# S151X.net
KiCad netlist of a schematic drawn in EAGLE
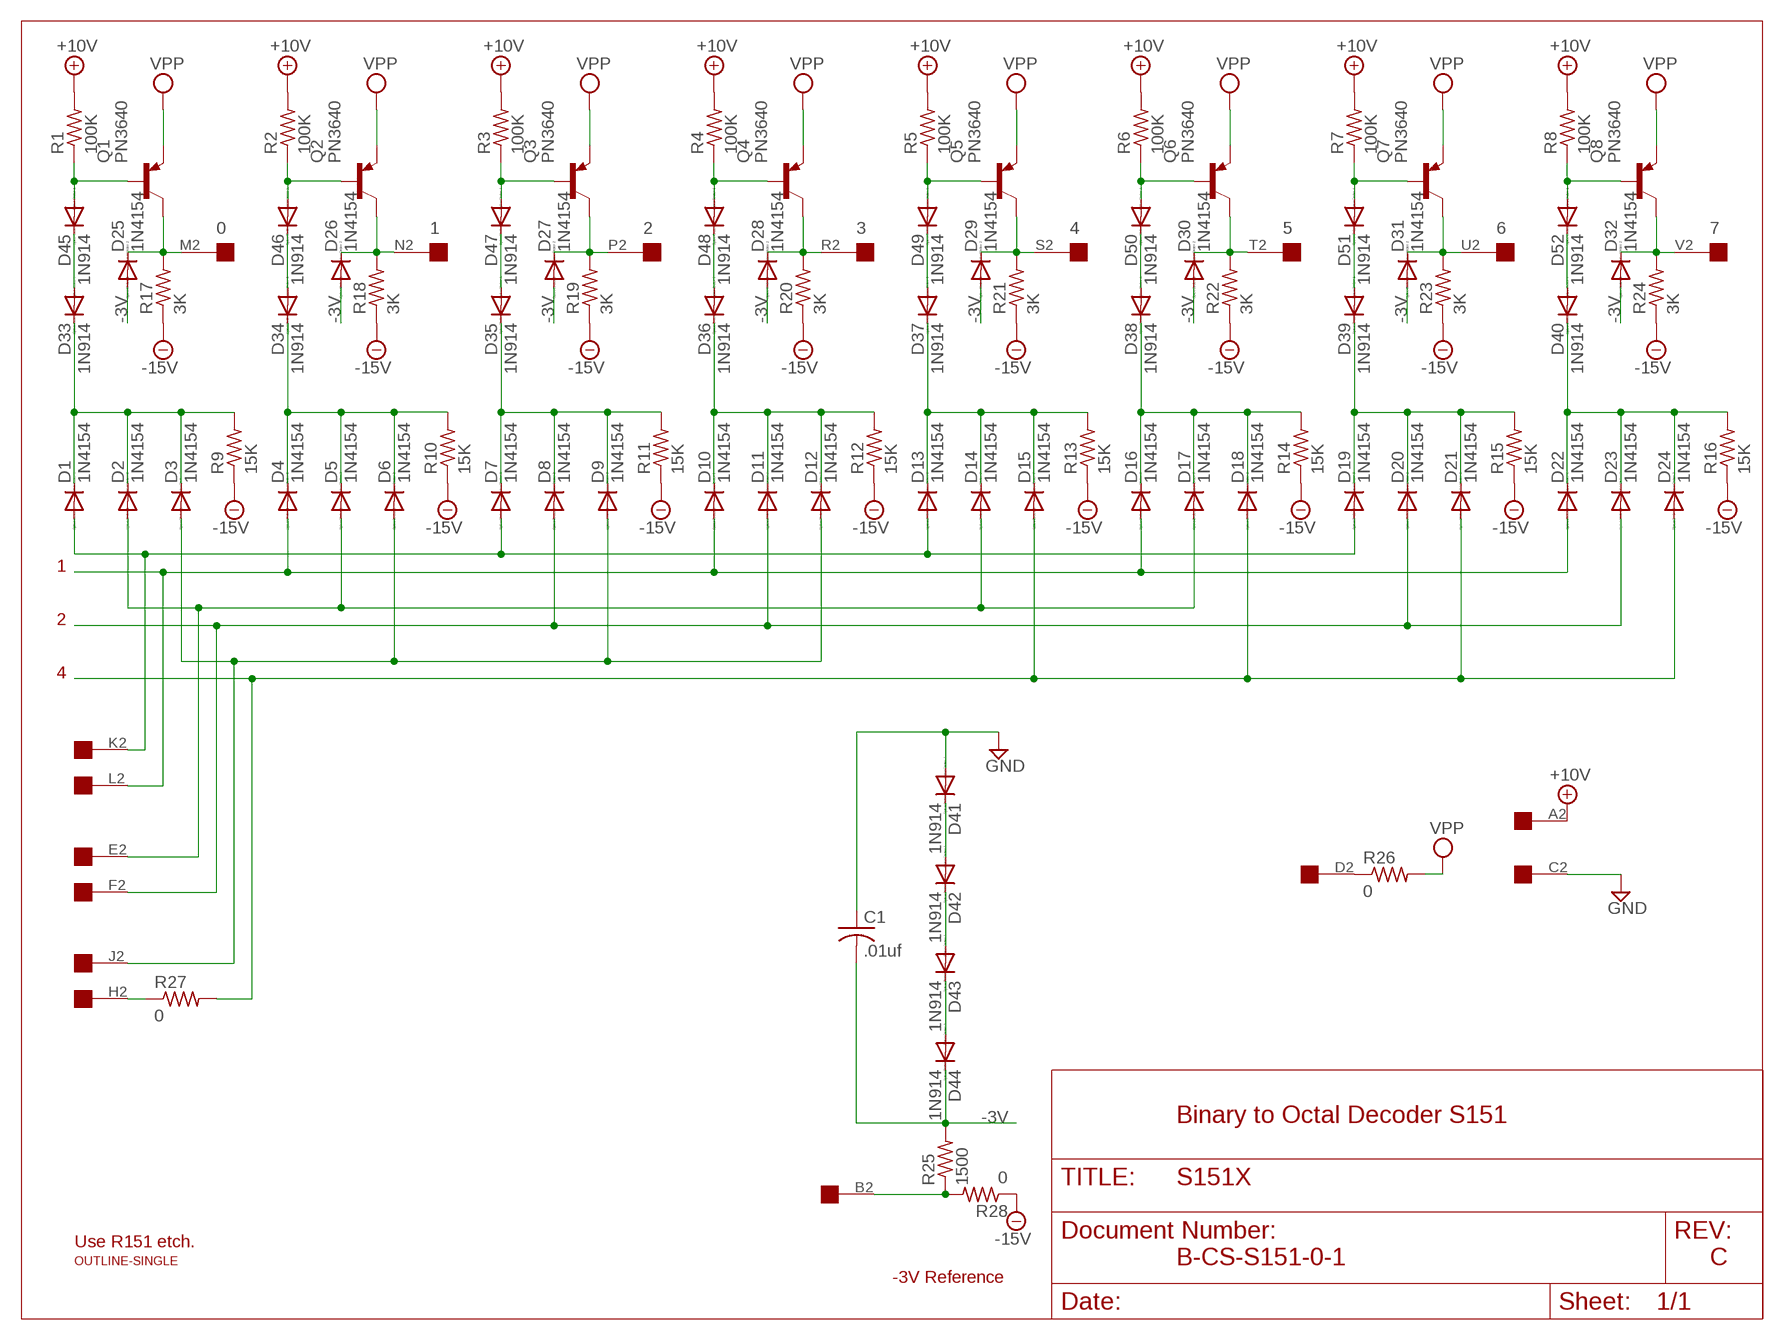
[diagram p0: schematic, sheet 1]

(export (version "E")
  (design (tool "Eeschema 10.0.6"))
  (components
    (comp (ref "C1")
      (value ".01uf")
      (footprint "eagle-import:C050-025X075")
      (libsource (lib "eagle-import") (part "C-US050-025X075"))
    )
    (comp (ref "D1")
      (value "1N4154")
      (footprint "eagle-import:DO35-10")
      (libsource (lib "eagle-import") (part "1N4148DO35-10"))
    )
    (comp (ref "D2")
      (value "1N4154")
      (footprint "eagle-import:DO35-10")
      (libsource (lib "eagle-import") (part "1N4148DO35-10"))
    )
    (comp (ref "D3")
      (value "1N4154")
      (footprint "eagle-import:DO35-10")
      (libsource (lib "eagle-import") (part "1N4148DO35-10"))
    )
    (comp (ref "D4")
      (value "1N4154")
      (footprint "eagle-import:DO35-10")
      (libsource (lib "eagle-import") (part "1N4148DO35-10"))
    )
    (comp (ref "D5")
      (value "1N4154")
      (footprint "eagle-import:DO35-10")
      (libsource (lib "eagle-import") (part "1N4148DO35-10"))
    )
    (comp (ref "D6")
      (value "1N4154")
      (footprint "eagle-import:DO35-10")
      (libsource (lib "eagle-import") (part "1N4148DO35-10"))
    )
    (comp (ref "D7")
      (value "1N4154")
      (footprint "eagle-import:DO35-10")
      (libsource (lib "eagle-import") (part "1N4148DO35-10"))
    )
    (comp (ref "D8")
      (value "1N4154")
      (footprint "eagle-import:DO35-10")
      (libsource (lib "eagle-import") (part "1N4148DO35-10"))
    )
    (comp (ref "D9")
      (value "1N4154")
      (footprint "eagle-import:DO35-10")
      (libsource (lib "eagle-import") (part "1N4148DO35-10"))
    )
    (comp (ref "D10")
      (value "1N4154")
      (footprint "eagle-import:DO35-10")
      (libsource (lib "eagle-import") (part "1N4148DO35-10"))
    )
    (comp (ref "D11")
      (value "1N4154")
      (footprint "eagle-import:DO35-10")
      (libsource (lib "eagle-import") (part "1N4148DO35-10"))
    )
    (comp (ref "D12")
      (value "1N4154")
      (footprint "eagle-import:DO35-10")
      (libsource (lib "eagle-import") (part "1N4148DO35-10"))
    )
    (comp (ref "D13")
      (value "1N4154")
      (footprint "eagle-import:DO35-10")
      (libsource (lib "eagle-import") (part "1N4148DO35-10"))
    )
    (comp (ref "D14")
      (value "1N4154")
      (footprint "eagle-import:DO35-10")
      (libsource (lib "eagle-import") (part "1N4148DO35-10"))
    )
    (comp (ref "D15")
      (value "1N4154")
      (footprint "eagle-import:DO35-10")
      (libsource (lib "eagle-import") (part "1N4148DO35-10"))
    )
    (comp (ref "D16")
      (value "1N4154")
      (footprint "eagle-import:DO35-10")
      (libsource (lib "eagle-import") (part "1N4148DO35-10"))
    )
    (comp (ref "D17")
      (value "1N4154")
      (footprint "eagle-import:DO35-10")
      (libsource (lib "eagle-import") (part "1N4148DO35-10"))
    )
    (comp (ref "D18")
      (value "1N4154")
      (footprint "eagle-import:DO35-10")
      (libsource (lib "eagle-import") (part "1N4148DO35-10"))
    )
    (comp (ref "D19")
      (value "1N4154")
      (footprint "eagle-import:DO35-10")
      (libsource (lib "eagle-import") (part "1N4148DO35-10"))
    )
    (comp (ref "D20")
      (value "1N4154")
      (footprint "eagle-import:DO35-10")
      (libsource (lib "eagle-import") (part "1N4148DO35-10"))
    )
    (comp (ref "D21")
      (value "1N4154")
      (footprint "eagle-import:DO35-10")
      (libsource (lib "eagle-import") (part "1N4148DO35-10"))
    )
    (comp (ref "D22")
      (value "1N4154")
      (footprint "eagle-import:DO35-10")
      (libsource (lib "eagle-import") (part "1N4148DO35-10"))
    )
    (comp (ref "D23")
      (value "1N4154")
      (footprint "eagle-import:DO35-10")
      (libsource (lib "eagle-import") (part "1N4148DO35-10"))
    )
    (comp (ref "D24")
      (value "1N4154")
      (footprint "eagle-import:DO35-10")
      (libsource (lib "eagle-import") (part "1N4148DO35-10"))
    )
    (comp (ref "D25")
      (value "1N4154")
      (footprint "eagle-import:DO35-10")
      (libsource (lib "eagle-import") (part "1N4148DO35-10"))
    )
    (comp (ref "D26")
      (value "1N4154")
      (footprint "eagle-import:DO35-10")
      (libsource (lib "eagle-import") (part "1N4148DO35-10"))
    )
    (comp (ref "D27")
      (value "1N4154")
      (footprint "eagle-import:DO35-10")
      (libsource (lib "eagle-import") (part "1N4148DO35-10"))
    )
    (comp (ref "D28")
      (value "1N4154")
      (footprint "eagle-import:DO35-10")
      (libsource (lib "eagle-import") (part "1N4148DO35-10"))
    )
    (comp (ref "D29")
      (value "1N4154")
      (footprint "eagle-import:DO35-10")
      (libsource (lib "eagle-import") (part "1N4148DO35-10"))
    )
    (comp (ref "D30")
      (value "1N4154")
      (footprint "eagle-import:DO35-10")
      (libsource (lib "eagle-import") (part "1N4148DO35-10"))
    )
    (comp (ref "D31")
      (value "1N4154")
      (footprint "eagle-import:DO35-10")
      (libsource (lib "eagle-import") (part "1N4148DO35-10"))
    )
    (comp (ref "D32")
      (value "1N4154")
      (footprint "eagle-import:DO35-10")
      (libsource (lib "eagle-import") (part "1N4148DO35-10"))
    )
    (comp (ref "D33")
      (value "1N914")
      (footprint "eagle-import:DO35-10")
      (libsource (lib "eagle-import") (part "1N4148DO35-10"))
    )
    (comp (ref "D34")
      (value "1N914")
      (footprint "eagle-import:DO35-10")
      (libsource (lib "eagle-import") (part "1N4148DO35-10"))
    )
    (comp (ref "D35")
      (value "1N914")
      (footprint "eagle-import:DO35-10")
      (libsource (lib "eagle-import") (part "1N4148DO35-10"))
    )
    (comp (ref "D36")
      (value "1N914")
      (footprint "eagle-import:DO35-10")
      (libsource (lib "eagle-import") (part "1N4148DO35-10"))
    )
    (comp (ref "D37")
      (value "1N914")
      (footprint "eagle-import:DO35-10")
      (libsource (lib "eagle-import") (part "1N4148DO35-10"))
    )
    (comp (ref "D38")
      (value "1N914")
      (footprint "eagle-import:DO35-10")
      (libsource (lib "eagle-import") (part "1N4148DO35-10"))
    )
    (comp (ref "D39")
      (value "1N914")
      (footprint "eagle-import:DO35-10")
      (libsource (lib "eagle-import") (part "1N4148DO35-10"))
    )
    (comp (ref "D40")
      (value "1N914")
      (footprint "eagle-import:DO35-10")
      (libsource (lib "eagle-import") (part "1N4148DO35-10"))
    )
    (comp (ref "D41")
      (value "1N914")
      (footprint "eagle-import:DO35-10")
      (libsource (lib "eagle-import") (part "1N4148DO35-10"))
    )
    (comp (ref "D42")
      (value "1N914")
      (footprint "eagle-import:DO35-10")
      (libsource (lib "eagle-import") (part "1N4148DO35-10"))
    )
    (comp (ref "D43")
      (value "1N914")
      (footprint "eagle-import:DO35-10")
      (libsource (lib "eagle-import") (part "1N4148DO35-10"))
    )
    (comp (ref "D44")
      (value "1N914")
      (footprint "eagle-import:DO35-10")
      (libsource (lib "eagle-import") (part "1N4148DO35-10"))
    )
    (comp (ref "D45")
      (value "1N914")
      (footprint "eagle-import:DO35-10")
      (libsource (lib "eagle-import") (part "1N4148DO35-10"))
    )
    (comp (ref "D46")
      (value "1N914")
      (footprint "eagle-import:DO35-10")
      (libsource (lib "eagle-import") (part "1N4148DO35-10"))
    )
    (comp (ref "D47")
      (value "1N914")
      (footprint "eagle-import:DO35-10")
      (libsource (lib "eagle-import") (part "1N4148DO35-10"))
    )
    (comp (ref "D48")
      (value "1N914")
      (footprint "eagle-import:DO35-10")
      (libsource (lib "eagle-import") (part "1N4148DO35-10"))
    )
    (comp (ref "D49")
      (value "1N914")
      (footprint "eagle-import:DO35-10")
      (libsource (lib "eagle-import") (part "1N4148DO35-10"))
    )
    (comp (ref "D50")
      (value "1N914")
      (footprint "eagle-import:DO35-10")
      (libsource (lib "eagle-import") (part "1N4148DO35-10"))
    )
    (comp (ref "D51")
      (value "1N914")
      (footprint "eagle-import:DO35-10")
      (libsource (lib "eagle-import") (part "1N4148DO35-10"))
    )
    (comp (ref "D52")
      (value "1N914")
      (footprint "eagle-import:DO35-10")
      (libsource (lib "eagle-import") (part "1N4148DO35-10"))
    )
    (comp (ref "Q1")
      (value "PN3640")
      (footprint "eagle-import:TO39")
      (libsource (lib "eagle-import") (part "2N3637"))
    )
    (comp (ref "Q2")
      (value "PN3640")
      (footprint "eagle-import:TO39")
      (libsource (lib "eagle-import") (part "2N3637"))
    )
    (comp (ref "Q3")
      (value "PN3640")
      (footprint "eagle-import:TO39")
      (libsource (lib "eagle-import") (part "2N3637"))
    )
    (comp (ref "Q4")
      (value "PN3640")
      (footprint "eagle-import:TO39")
      (libsource (lib "eagle-import") (part "2N3637"))
    )
    (comp (ref "Q5")
      (value "PN3640")
      (footprint "eagle-import:TO39")
      (libsource (lib "eagle-import") (part "2N3637"))
    )
    (comp (ref "Q6")
      (value "PN3640")
      (footprint "eagle-import:TO39")
      (libsource (lib "eagle-import") (part "2N3637"))
    )
    (comp (ref "Q7")
      (value "PN3640")
      (footprint "eagle-import:TO39")
      (libsource (lib "eagle-import") (part "2N3637"))
    )
    (comp (ref "Q8")
      (value "PN3640")
      (footprint "eagle-import:TO39")
      (libsource (lib "eagle-import") (part "2N3637"))
    )
    (comp (ref "R1")
      (value "100K")
      (footprint "eagle-import:0207_10")
      (libsource (lib "eagle-import") (part "R-US_0207/10"))
    )
    (comp (ref "R2")
      (value "100K")
      (footprint "eagle-import:0207_10")
      (libsource (lib "eagle-import") (part "R-US_0207/10"))
    )
    (comp (ref "R3")
      (value "100K")
      (footprint "eagle-import:0207_10")
      (libsource (lib "eagle-import") (part "R-US_0207/10"))
    )
    (comp (ref "R4")
      (value "100K")
      (footprint "eagle-import:0207_10")
      (libsource (lib "eagle-import") (part "R-US_0207/10"))
    )
    (comp (ref "R5")
      (value "100K")
      (footprint "eagle-import:0207_10")
      (libsource (lib "eagle-import") (part "R-US_0207/10"))
    )
    (comp (ref "R6")
      (value "100K")
      (footprint "eagle-import:0207_10")
      (libsource (lib "eagle-import") (part "R-US_0207/10"))
    )
    (comp (ref "R7")
      (value "100K")
      (footprint "eagle-import:0207_10")
      (libsource (lib "eagle-import") (part "R-US_0207/10"))
    )
    (comp (ref "R8")
      (value "100K")
      (footprint "eagle-import:0207_10")
      (libsource (lib "eagle-import") (part "R-US_0207/10"))
    )
    (comp (ref "R9")
      (value "15K")
      (footprint "eagle-import:0207_10")
      (libsource (lib "eagle-import") (part "R-US_0207/10"))
    )
    (comp (ref "R10")
      (value "15K")
      (footprint "eagle-import:0207_10")
      (libsource (lib "eagle-import") (part "R-US_0207/10"))
    )
    (comp (ref "R11")
      (value "15K")
      (footprint "eagle-import:0207_10")
      (libsource (lib "eagle-import") (part "R-US_0207/10"))
    )
    (comp (ref "R12")
      (value "15K")
      (footprint "eagle-import:0207_10")
      (libsource (lib "eagle-import") (part "R-US_0207/10"))
    )
    (comp (ref "R13")
      (value "15K")
      (footprint "eagle-import:0207_10")
      (libsource (lib "eagle-import") (part "R-US_0207/10"))
    )
    (comp (ref "R14")
      (value "15K")
      (footprint "eagle-import:0207_10")
      (libsource (lib "eagle-import") (part "R-US_0207/10"))
    )
    (comp (ref "R15")
      (value "15K")
      (footprint "eagle-import:0207_10")
      (libsource (lib "eagle-import") (part "R-US_0207/10"))
    )
    (comp (ref "R16")
      (value "15K")
      (footprint "eagle-import:0207_10")
      (libsource (lib "eagle-import") (part "R-US_0207/10"))
    )
    (comp (ref "R17")
      (value "3K")
      (footprint "eagle-import:0207_10")
      (libsource (lib "eagle-import") (part "R-US_0207/10"))
    )
    (comp (ref "R18")
      (value "3K")
      (footprint "eagle-import:0207_10")
      (libsource (lib "eagle-import") (part "R-US_0207/10"))
    )
    (comp (ref "R19")
      (value "3K")
      (footprint "eagle-import:0207_10")
      (libsource (lib "eagle-import") (part "R-US_0207/10"))
    )
    (comp (ref "R20")
      (value "3K")
      (footprint "eagle-import:0207_10")
      (libsource (lib "eagle-import") (part "R-US_0207/10"))
    )
    (comp (ref "R21")
      (value "3K")
      (footprint "eagle-import:0207_10")
      (libsource (lib "eagle-import") (part "R-US_0207/10"))
    )
    (comp (ref "R22")
      (value "3K")
      (footprint "eagle-import:0207_10")
      (libsource (lib "eagle-import") (part "R-US_0207/10"))
    )
    (comp (ref "R23")
      (value "3K")
      (footprint "eagle-import:0207_10")
      (libsource (lib "eagle-import") (part "R-US_0207/10"))
    )
    (comp (ref "R24")
      (value "3K")
      (footprint "eagle-import:0207_10")
      (libsource (lib "eagle-import") (part "R-US_0207/10"))
    )
    (comp (ref "R25")
      (value "1500")
      (footprint "eagle-import:0207_10")
      (libsource (lib "eagle-import") (part "R-US_0207/10"))
    )
    (comp (ref "R26")
      (value "0")
      (footprint "eagle-import:0207_10")
      (libsource (lib "eagle-import") (part "R-US_0207/10"))
    )
    (comp (ref "R27")
      (value "0")
      (footprint "eagle-import:0207_10")
      (libsource (lib "eagle-import") (part "R-US_0207/10"))
    )
    (comp (ref "R28")
      (value "0")
      (footprint "eagle-import:0207_10")
      (libsource (lib "eagle-import") (part "R-US_0207/10"))
    )
    (comp (ref "U$1")
      (value "OUTLINE-SINGLE")
      (footprint "eagle-import:SINGLE")
      (libsource (lib "eagle-import") (part "OUTLINE-SINGLE"))
    )
    (comp (ref "U$2")
      (value "EDGE-1")
      (footprint "eagle-import:EDGE-CON1")
      (libsource (lib "eagle-import") (part "EDGE-1"))
    )
  )
  (nets
    (net (code "1") (name "+10V") (class "Default")
      (node (ref "R1") (pin "2") (pinfunction "2_2") (pintype "passive"))
      (node (ref "R2") (pin "2") (pinfunction "2_2") (pintype "passive"))
      (node (ref "R3") (pin "2") (pinfunction "2_2") (pintype "passive"))
      (node (ref "R4") (pin "2") (pinfunction "2_2") (pintype "passive"))
      (node (ref "R5") (pin "2") (pinfunction "2_2") (pintype "passive"))
      (node (ref "R6") (pin "2") (pinfunction "2_2") (pintype "passive"))
      (node (ref "R7") (pin "2") (pinfunction "2_2") (pintype "passive"))
      (node (ref "R8") (pin "2") (pinfunction "2_2") (pintype "passive"))
      (node (ref "U$2") (pin "A2") (pinfunction "1_A2") (pintype "bidirectional"))
    )
    (net (code "2") (name "-15V") (class "Default")
      (node (ref "R10") (pin "1") (pinfunction "1_1") (pintype "passive"))
      (node (ref "R11") (pin "1") (pinfunction "1_1") (pintype "passive"))
      (node (ref "R12") (pin "1") (pinfunction "1_1") (pintype "passive"))
      (node (ref "R13") (pin "1") (pinfunction "1_1") (pintype "passive"))
      (node (ref "R14") (pin "1") (pinfunction "1_1") (pintype "passive"))
      (node (ref "R15") (pin "1") (pinfunction "1_1") (pintype "passive"))
      (node (ref "R16") (pin "1") (pinfunction "1_1") (pintype "passive"))
      (node (ref "R17") (pin "1") (pinfunction "1_1") (pintype "passive"))
      (node (ref "R18") (pin "1") (pinfunction "1_1") (pintype "passive"))
      (node (ref "R19") (pin "1") (pinfunction "1_1") (pintype "passive"))
      (node (ref "R20") (pin "1") (pinfunction "1_1") (pintype "passive"))
      (node (ref "R21") (pin "1") (pinfunction "1_1") (pintype "passive"))
      (node (ref "R22") (pin "1") (pinfunction "1_1") (pintype "passive"))
      (node (ref "R23") (pin "1") (pinfunction "1_1") (pintype "passive"))
      (node (ref "R24") (pin "1") (pinfunction "1_1") (pintype "passive"))
      (node (ref "R28") (pin "1") (pinfunction "1_1") (pintype "passive"))
      (node (ref "R9") (pin "1") (pinfunction "1_1") (pintype "passive"))
    )
    (net (code "3") (name "/-3V") (class "Default")
      (node (ref "C1") (pin "2") (pinfunction "2_2") (pintype "passive"))
      (node (ref "D25") (pin "A") (pinfunction "A_A") (pintype "passive"))
      (node (ref "D26") (pin "A") (pinfunction "A_A") (pintype "passive"))
      (node (ref "D27") (pin "A") (pinfunction "A_A") (pintype "passive"))
      (node (ref "D28") (pin "A") (pinfunction "A_A") (pintype "passive"))
      (node (ref "D29") (pin "A") (pinfunction "A_A") (pintype "passive"))
      (node (ref "D30") (pin "A") (pinfunction "A_A") (pintype "passive"))
      (node (ref "D31") (pin "A") (pinfunction "A_A") (pintype "passive"))
      (node (ref "D32") (pin "A") (pinfunction "A_A") (pintype "passive"))
      (node (ref "D44") (pin "C") (pinfunction "C_C") (pintype "passive"))
      (node (ref "R25") (pin "2") (pinfunction "2_2") (pintype "passive"))
    )
    (net (code "4") (name "/0") (class "Default")
      (node (ref "D25") (pin "C") (pinfunction "C_C") (pintype "passive"))
      (node (ref "Q1") (pin "3") (pinfunction "C_3") (pintype "passive"))
      (node (ref "R17") (pin "2") (pinfunction "2_2") (pintype "passive"))
      (node (ref "U$2") (pin "M2") (pinfunction "1_M2") (pintype "bidirectional"))
    )
    (net (code "5") (name "/1") (class "Default")
      (node (ref "D26") (pin "C") (pinfunction "C_C") (pintype "passive"))
      (node (ref "Q2") (pin "3") (pinfunction "C_3") (pintype "passive"))
      (node (ref "R18") (pin "2") (pinfunction "2_2") (pintype "passive"))
      (node (ref "U$2") (pin "N2") (pinfunction "1_N2") (pintype "bidirectional"))
    )
    (net (code "6") (name "/2") (class "Default")
      (node (ref "D27") (pin "C") (pinfunction "C_C") (pintype "passive"))
      (node (ref "Q3") (pin "3") (pinfunction "C_3") (pintype "passive"))
      (node (ref "R19") (pin "2") (pinfunction "2_2") (pintype "passive"))
      (node (ref "U$2") (pin "P2") (pinfunction "1_P2") (pintype "bidirectional"))
    )
    (net (code "7") (name "/3") (class "Default")
      (node (ref "D28") (pin "C") (pinfunction "C_C") (pintype "passive"))
      (node (ref "Q4") (pin "3") (pinfunction "C_3") (pintype "passive"))
      (node (ref "R20") (pin "2") (pinfunction "2_2") (pintype "passive"))
      (node (ref "U$2") (pin "R2") (pinfunction "1_R2") (pintype "bidirectional"))
    )
    (net (code "8") (name "/4") (class "Default")
      (node (ref "D29") (pin "C") (pinfunction "C_C") (pintype "passive"))
      (node (ref "Q5") (pin "3") (pinfunction "C_3") (pintype "passive"))
      (node (ref "R21") (pin "2") (pinfunction "2_2") (pintype "passive"))
      (node (ref "U$2") (pin "S2") (pinfunction "1_S2") (pintype "bidirectional"))
    )
    (net (code "9") (name "/5") (class "Default")
      (node (ref "D30") (pin "C") (pinfunction "C_C") (pintype "passive"))
      (node (ref "Q6") (pin "3") (pinfunction "C_3") (pintype "passive"))
      (node (ref "R22") (pin "2") (pinfunction "2_2") (pintype "passive"))
      (node (ref "U$2") (pin "T2") (pinfunction "1_T2") (pintype "bidirectional"))
    )
    (net (code "10") (name "/6") (class "Default")
      (node (ref "D31") (pin "C") (pinfunction "C_C") (pintype "passive"))
      (node (ref "Q7") (pin "3") (pinfunction "C_3") (pintype "passive"))
      (node (ref "R23") (pin "2") (pinfunction "2_2") (pintype "passive"))
      (node (ref "U$2") (pin "U2") (pinfunction "1_U2") (pintype "bidirectional"))
    )
    (net (code "11") (name "/7") (class "Default")
      (node (ref "D32") (pin "C") (pinfunction "C_C") (pintype "passive"))
      (node (ref "Q8") (pin "3") (pinfunction "C_3") (pintype "passive"))
      (node (ref "R24") (pin "2") (pinfunction "2_2") (pintype "passive"))
      (node (ref "U$2") (pin "V2") (pinfunction "1_V2") (pintype "bidirectional"))
    )
    (net (code "12") (name "GND") (class "Default")
      (node (ref "C1") (pin "1") (pinfunction "1_1") (pintype "passive"))
      (node (ref "D41") (pin "A") (pinfunction "A_A") (pintype "passive"))
      (node (ref "U$2") (pin "C2") (pinfunction "1_C2") (pintype "bidirectional"))
    )
    (net (code "13") (name "Net-(D1-PadC)") (class "Default")
      (node (ref "D1") (pin "C") (pinfunction "C_C") (pintype "passive"))
      (node (ref "D2") (pin "C") (pinfunction "C_C") (pintype "passive"))
      (node (ref "D3") (pin "C") (pinfunction "C_C") (pintype "passive"))
      (node (ref "D33") (pin "C") (pinfunction "C_C") (pintype "passive"))
      (node (ref "R9") (pin "2") (pinfunction "2_2") (pintype "passive"))
    )
    (net (code "14") (name "Net-(D10-PadC)") (class "Default")
      (node (ref "D10") (pin "C") (pinfunction "C_C") (pintype "passive"))
      (node (ref "D11") (pin "C") (pinfunction "C_C") (pintype "passive"))
      (node (ref "D12") (pin "C") (pinfunction "C_C") (pintype "passive"))
      (node (ref "D36") (pin "C") (pinfunction "C_C") (pintype "passive"))
      (node (ref "R12") (pin "2") (pinfunction "2_2") (pintype "passive"))
    )
    (net (code "15") (name "Net-(D13-PadC)") (class "Default")
      (node (ref "D13") (pin "C") (pinfunction "C_C") (pintype "passive"))
      (node (ref "D14") (pin "C") (pinfunction "C_C") (pintype "passive"))
      (node (ref "D15") (pin "C") (pinfunction "C_C") (pintype "passive"))
      (node (ref "D37") (pin "C") (pinfunction "C_C") (pintype "passive"))
      (node (ref "R13") (pin "2") (pinfunction "2_2") (pintype "passive"))
    )
    (net (code "16") (name "Net-(D15-PadA)") (class "Default")
      (node (ref "D15") (pin "A") (pinfunction "A_A") (pintype "passive"))
      (node (ref "D18") (pin "A") (pinfunction "A_A") (pintype "passive"))
      (node (ref "D21") (pin "A") (pinfunction "A_A") (pintype "passive"))
      (node (ref "D24") (pin "A") (pinfunction "A_A") (pintype "passive"))
      (node (ref "R27") (pin "2") (pinfunction "2_2") (pintype "passive"))
    )
    (net (code "17") (name "Net-(D16-PadC)") (class "Default")
      (node (ref "D16") (pin "C") (pinfunction "C_C") (pintype "passive"))
      (node (ref "D17") (pin "C") (pinfunction "C_C") (pintype "passive"))
      (node (ref "D18") (pin "C") (pinfunction "C_C") (pintype "passive"))
      (node (ref "D38") (pin "C") (pinfunction "C_C") (pintype "passive"))
      (node (ref "R14") (pin "2") (pinfunction "2_2") (pintype "passive"))
    )
    (net (code "18") (name "Net-(D19-PadC)") (class "Default")
      (node (ref "D19") (pin "C") (pinfunction "C_C") (pintype "passive"))
      (node (ref "D20") (pin "C") (pinfunction "C_C") (pintype "passive"))
      (node (ref "D21") (pin "C") (pinfunction "C_C") (pintype "passive"))
      (node (ref "D39") (pin "C") (pinfunction "C_C") (pintype "passive"))
      (node (ref "R15") (pin "2") (pinfunction "2_2") (pintype "passive"))
    )
    (net (code "19") (name "Net-(D22-PadC)") (class "Default")
      (node (ref "D22") (pin "C") (pinfunction "C_C") (pintype "passive"))
      (node (ref "D23") (pin "C") (pinfunction "C_C") (pintype "passive"))
      (node (ref "D24") (pin "C") (pinfunction "C_C") (pintype "passive"))
      (node (ref "D40") (pin "C") (pinfunction "C_C") (pintype "passive"))
      (node (ref "R16") (pin "2") (pinfunction "2_2") (pintype "passive"))
    )
    (net (code "20") (name "Net-(D33-PadA)") (class "Default")
      (node (ref "D33") (pin "A") (pinfunction "A_A") (pintype "passive"))
      (node (ref "D45") (pin "C") (pinfunction "C_C") (pintype "passive"))
    )
    (net (code "21") (name "Net-(D34-PadA)") (class "Default")
      (node (ref "D34") (pin "A") (pinfunction "A_A") (pintype "passive"))
      (node (ref "D46") (pin "C") (pinfunction "C_C") (pintype "passive"))
    )
    (net (code "22") (name "Net-(D34-PadC)") (class "Default")
      (node (ref "D34") (pin "C") (pinfunction "C_C") (pintype "passive"))
      (node (ref "D4") (pin "C") (pinfunction "C_C") (pintype "passive"))
      (node (ref "D5") (pin "C") (pinfunction "C_C") (pintype "passive"))
      (node (ref "D6") (pin "C") (pinfunction "C_C") (pintype "passive"))
      (node (ref "R10") (pin "2") (pinfunction "2_2") (pintype "passive"))
    )
    (net (code "23") (name "Net-(D35-PadA)") (class "Default")
      (node (ref "D35") (pin "A") (pinfunction "A_A") (pintype "passive"))
      (node (ref "D47") (pin "C") (pinfunction "C_C") (pintype "passive"))
    )
    (net (code "24") (name "Net-(D35-PadC)") (class "Default")
      (node (ref "D35") (pin "C") (pinfunction "C_C") (pintype "passive"))
      (node (ref "D7") (pin "C") (pinfunction "C_C") (pintype "passive"))
      (node (ref "D8") (pin "C") (pinfunction "C_C") (pintype "passive"))
      (node (ref "D9") (pin "C") (pinfunction "C_C") (pintype "passive"))
      (node (ref "R11") (pin "2") (pinfunction "2_2") (pintype "passive"))
    )
    (net (code "25") (name "Net-(D36-PadA)") (class "Default")
      (node (ref "D36") (pin "A") (pinfunction "A_A") (pintype "passive"))
      (node (ref "D48") (pin "C") (pinfunction "C_C") (pintype "passive"))
    )
    (net (code "26") (name "Net-(D37-PadA)") (class "Default")
      (node (ref "D37") (pin "A") (pinfunction "A_A") (pintype "passive"))
      (node (ref "D49") (pin "C") (pinfunction "C_C") (pintype "passive"))
    )
    (net (code "27") (name "Net-(D38-PadA)") (class "Default")
      (node (ref "D38") (pin "A") (pinfunction "A_A") (pintype "passive"))
      (node (ref "D50") (pin "C") (pinfunction "C_C") (pintype "passive"))
    )
    (net (code "28") (name "Net-(D39-PadA)") (class "Default")
      (node (ref "D39") (pin "A") (pinfunction "A_A") (pintype "passive"))
      (node (ref "D51") (pin "C") (pinfunction "C_C") (pintype "passive"))
    )
    (net (code "29") (name "Net-(D40-PadA)") (class "Default")
      (node (ref "D40") (pin "A") (pinfunction "A_A") (pintype "passive"))
      (node (ref "D52") (pin "C") (pinfunction "C_C") (pintype "passive"))
    )
    (net (code "30") (name "Net-(D41-PadC)") (class "Default")
      (node (ref "D41") (pin "C") (pinfunction "C_C") (pintype "passive"))
      (node (ref "D42") (pin "A") (pinfunction "A_A") (pintype "passive"))
    )
    (net (code "31") (name "Net-(D42-PadC)") (class "Default")
      (node (ref "D42") (pin "C") (pinfunction "C_C") (pintype "passive"))
      (node (ref "D43") (pin "A") (pinfunction "A_A") (pintype "passive"))
    )
    (net (code "32") (name "Net-(D43-PadC)") (class "Default")
      (node (ref "D43") (pin "C") (pinfunction "C_C") (pintype "passive"))
      (node (ref "D44") (pin "A") (pinfunction "A_A") (pintype "passive"))
    )
    (net (code "33") (name "Net-(Q1-B)") (class "Default")
      (node (ref "D45") (pin "A") (pinfunction "A_A") (pintype "passive"))
      (node (ref "Q1") (pin "2") (pinfunction "B_2") (pintype "passive"))
      (node (ref "R1") (pin "1") (pinfunction "1_1") (pintype "passive"))
    )
    (net (code "34") (name "Net-(Q2-B)") (class "Default")
      (node (ref "D46") (pin "A") (pinfunction "A_A") (pintype "passive"))
      (node (ref "Q2") (pin "2") (pinfunction "B_2") (pintype "passive"))
      (node (ref "R2") (pin "1") (pinfunction "1_1") (pintype "passive"))
    )
    (net (code "35") (name "Net-(Q3-B)") (class "Default")
      (node (ref "D47") (pin "A") (pinfunction "A_A") (pintype "passive"))
      (node (ref "Q3") (pin "2") (pinfunction "B_2") (pintype "passive"))
      (node (ref "R3") (pin "1") (pinfunction "1_1") (pintype "passive"))
    )
    (net (code "36") (name "Net-(Q4-B)") (class "Default")
      (node (ref "D48") (pin "A") (pinfunction "A_A") (pintype "passive"))
      (node (ref "Q4") (pin "2") (pinfunction "B_2") (pintype "passive"))
      (node (ref "R4") (pin "1") (pinfunction "1_1") (pintype "passive"))
    )
    (net (code "37") (name "Net-(Q5-B)") (class "Default")
      (node (ref "D49") (pin "A") (pinfunction "A_A") (pintype "passive"))
      (node (ref "Q5") (pin "2") (pinfunction "B_2") (pintype "passive"))
      (node (ref "R5") (pin "1") (pinfunction "1_1") (pintype "passive"))
    )
    (net (code "38") (name "Net-(Q6-B)") (class "Default")
      (node (ref "D50") (pin "A") (pinfunction "A_A") (pintype "passive"))
      (node (ref "Q6") (pin "2") (pinfunction "B_2") (pintype "passive"))
      (node (ref "R6") (pin "1") (pinfunction "1_1") (pintype "passive"))
    )
    (net (code "39") (name "Net-(Q7-B)") (class "Default")
      (node (ref "D51") (pin "A") (pinfunction "A_A") (pintype "passive"))
      (node (ref "Q7") (pin "2") (pinfunction "B_2") (pintype "passive"))
      (node (ref "R7") (pin "1") (pinfunction "1_1") (pintype "passive"))
    )
    (net (code "40") (name "Net-(Q8-B)") (class "Default")
      (node (ref "D52") (pin "A") (pinfunction "A_A") (pintype "passive"))
      (node (ref "Q8") (pin "2") (pinfunction "B_2") (pintype "passive"))
      (node (ref "R8") (pin "1") (pinfunction "1_1") (pintype "passive"))
    )
    (net (code "41") (name "Net-(U$2B-1)") (class "Default")
      (node (ref "R25") (pin "1") (pinfunction "1_1") (pintype "passive"))
      (node (ref "R28") (pin "2") (pinfunction "2_2") (pintype "passive"))
      (node (ref "U$2") (pin "B2") (pinfunction "1_B2") (pintype "bidirectional"))
    )
    (net (code "42") (name "Net-(U$2D-1)") (class "Default")
      (node (ref "R26") (pin "1") (pinfunction "1_1") (pintype "passive"))
      (node (ref "U$2") (pin "D2") (pinfunction "1_D2") (pintype "bidirectional"))
    )
    (net (code "43") (name "Net-(U$2E-1)") (class "Default")
      (node (ref "D14") (pin "A") (pinfunction "A_A") (pintype "passive"))
      (node (ref "D17") (pin "A") (pinfunction "A_A") (pintype "passive"))
      (node (ref "D2") (pin "A") (pinfunction "A_A") (pintype "passive"))
      (node (ref "D5") (pin "A") (pinfunction "A_A") (pintype "passive"))
      (node (ref "U$2") (pin "E2") (pinfunction "1_E2") (pintype "bidirectional"))
    )
    (net (code "44") (name "Net-(U$2F-1)") (class "Default")
      (node (ref "D11") (pin "A") (pinfunction "A_A") (pintype "passive"))
      (node (ref "D20") (pin "A") (pinfunction "A_A") (pintype "passive"))
      (node (ref "D23") (pin "A") (pinfunction "A_A") (pintype "passive"))
      (node (ref "D8") (pin "A") (pinfunction "A_A") (pintype "passive"))
      (node (ref "U$2") (pin "F2") (pinfunction "1_F2") (pintype "bidirectional"))
    )
    (net (code "45") (name "Net-(U$2G-1)") (class "Default")
      (node (ref "R27") (pin "1") (pinfunction "1_1") (pintype "passive"))
      (node (ref "U$2") (pin "H2") (pinfunction "1_H2") (pintype "bidirectional"))
    )
    (net (code "46") (name "Net-(U$2H-1)") (class "Default")
      (node (ref "D12") (pin "A") (pinfunction "A_A") (pintype "passive"))
      (node (ref "D3") (pin "A") (pinfunction "A_A") (pintype "passive"))
      (node (ref "D6") (pin "A") (pinfunction "A_A") (pintype "passive"))
      (node (ref "D9") (pin "A") (pinfunction "A_A") (pintype "passive"))
      (node (ref "U$2") (pin "J2") (pinfunction "1_J2") (pintype "bidirectional"))
    )
    (net (code "47") (name "Net-(U$2I-1)") (class "Default")
      (node (ref "D1") (pin "A") (pinfunction "A_A") (pintype "passive"))
      (node (ref "D13") (pin "A") (pinfunction "A_A") (pintype "passive"))
      (node (ref "D19") (pin "A") (pinfunction "A_A") (pintype "passive"))
      (node (ref "D7") (pin "A") (pinfunction "A_A") (pintype "passive"))
      (node (ref "U$2") (pin "K2") (pinfunction "1_K2") (pintype "bidirectional"))
    )
    (net (code "48") (name "Net-(U$2J-1)") (class "Default")
      (node (ref "D10") (pin "A") (pinfunction "A_A") (pintype "passive"))
      (node (ref "D16") (pin "A") (pinfunction "A_A") (pintype "passive"))
      (node (ref "D22") (pin "A") (pinfunction "A_A") (pintype "passive"))
      (node (ref "D4") (pin "A") (pinfunction "A_A") (pintype "passive"))
      (node (ref "U$2") (pin "L2") (pinfunction "1_L2") (pintype "bidirectional"))
    )
    (net (code "49") (name "VPP") (class "Default")
      (node (ref "Q1") (pin "1") (pinfunction "E_1") (pintype "passive"))
      (node (ref "Q2") (pin "1") (pinfunction "E_1") (pintype "passive"))
      (node (ref "Q3") (pin "1") (pinfunction "E_1") (pintype "passive"))
      (node (ref "Q4") (pin "1") (pinfunction "E_1") (pintype "passive"))
      (node (ref "Q5") (pin "1") (pinfunction "E_1") (pintype "passive"))
      (node (ref "Q6") (pin "1") (pinfunction "E_1") (pintype "passive"))
      (node (ref "Q7") (pin "1") (pinfunction "E_1") (pintype "passive"))
      (node (ref "Q8") (pin "1") (pinfunction "E_1") (pintype "passive"))
      (node (ref "R26") (pin "2") (pinfunction "2_2") (pintype "passive"))
    )
  )
)
